# Power.net
KiCad netlist of a schematic drawn in Altium Designer
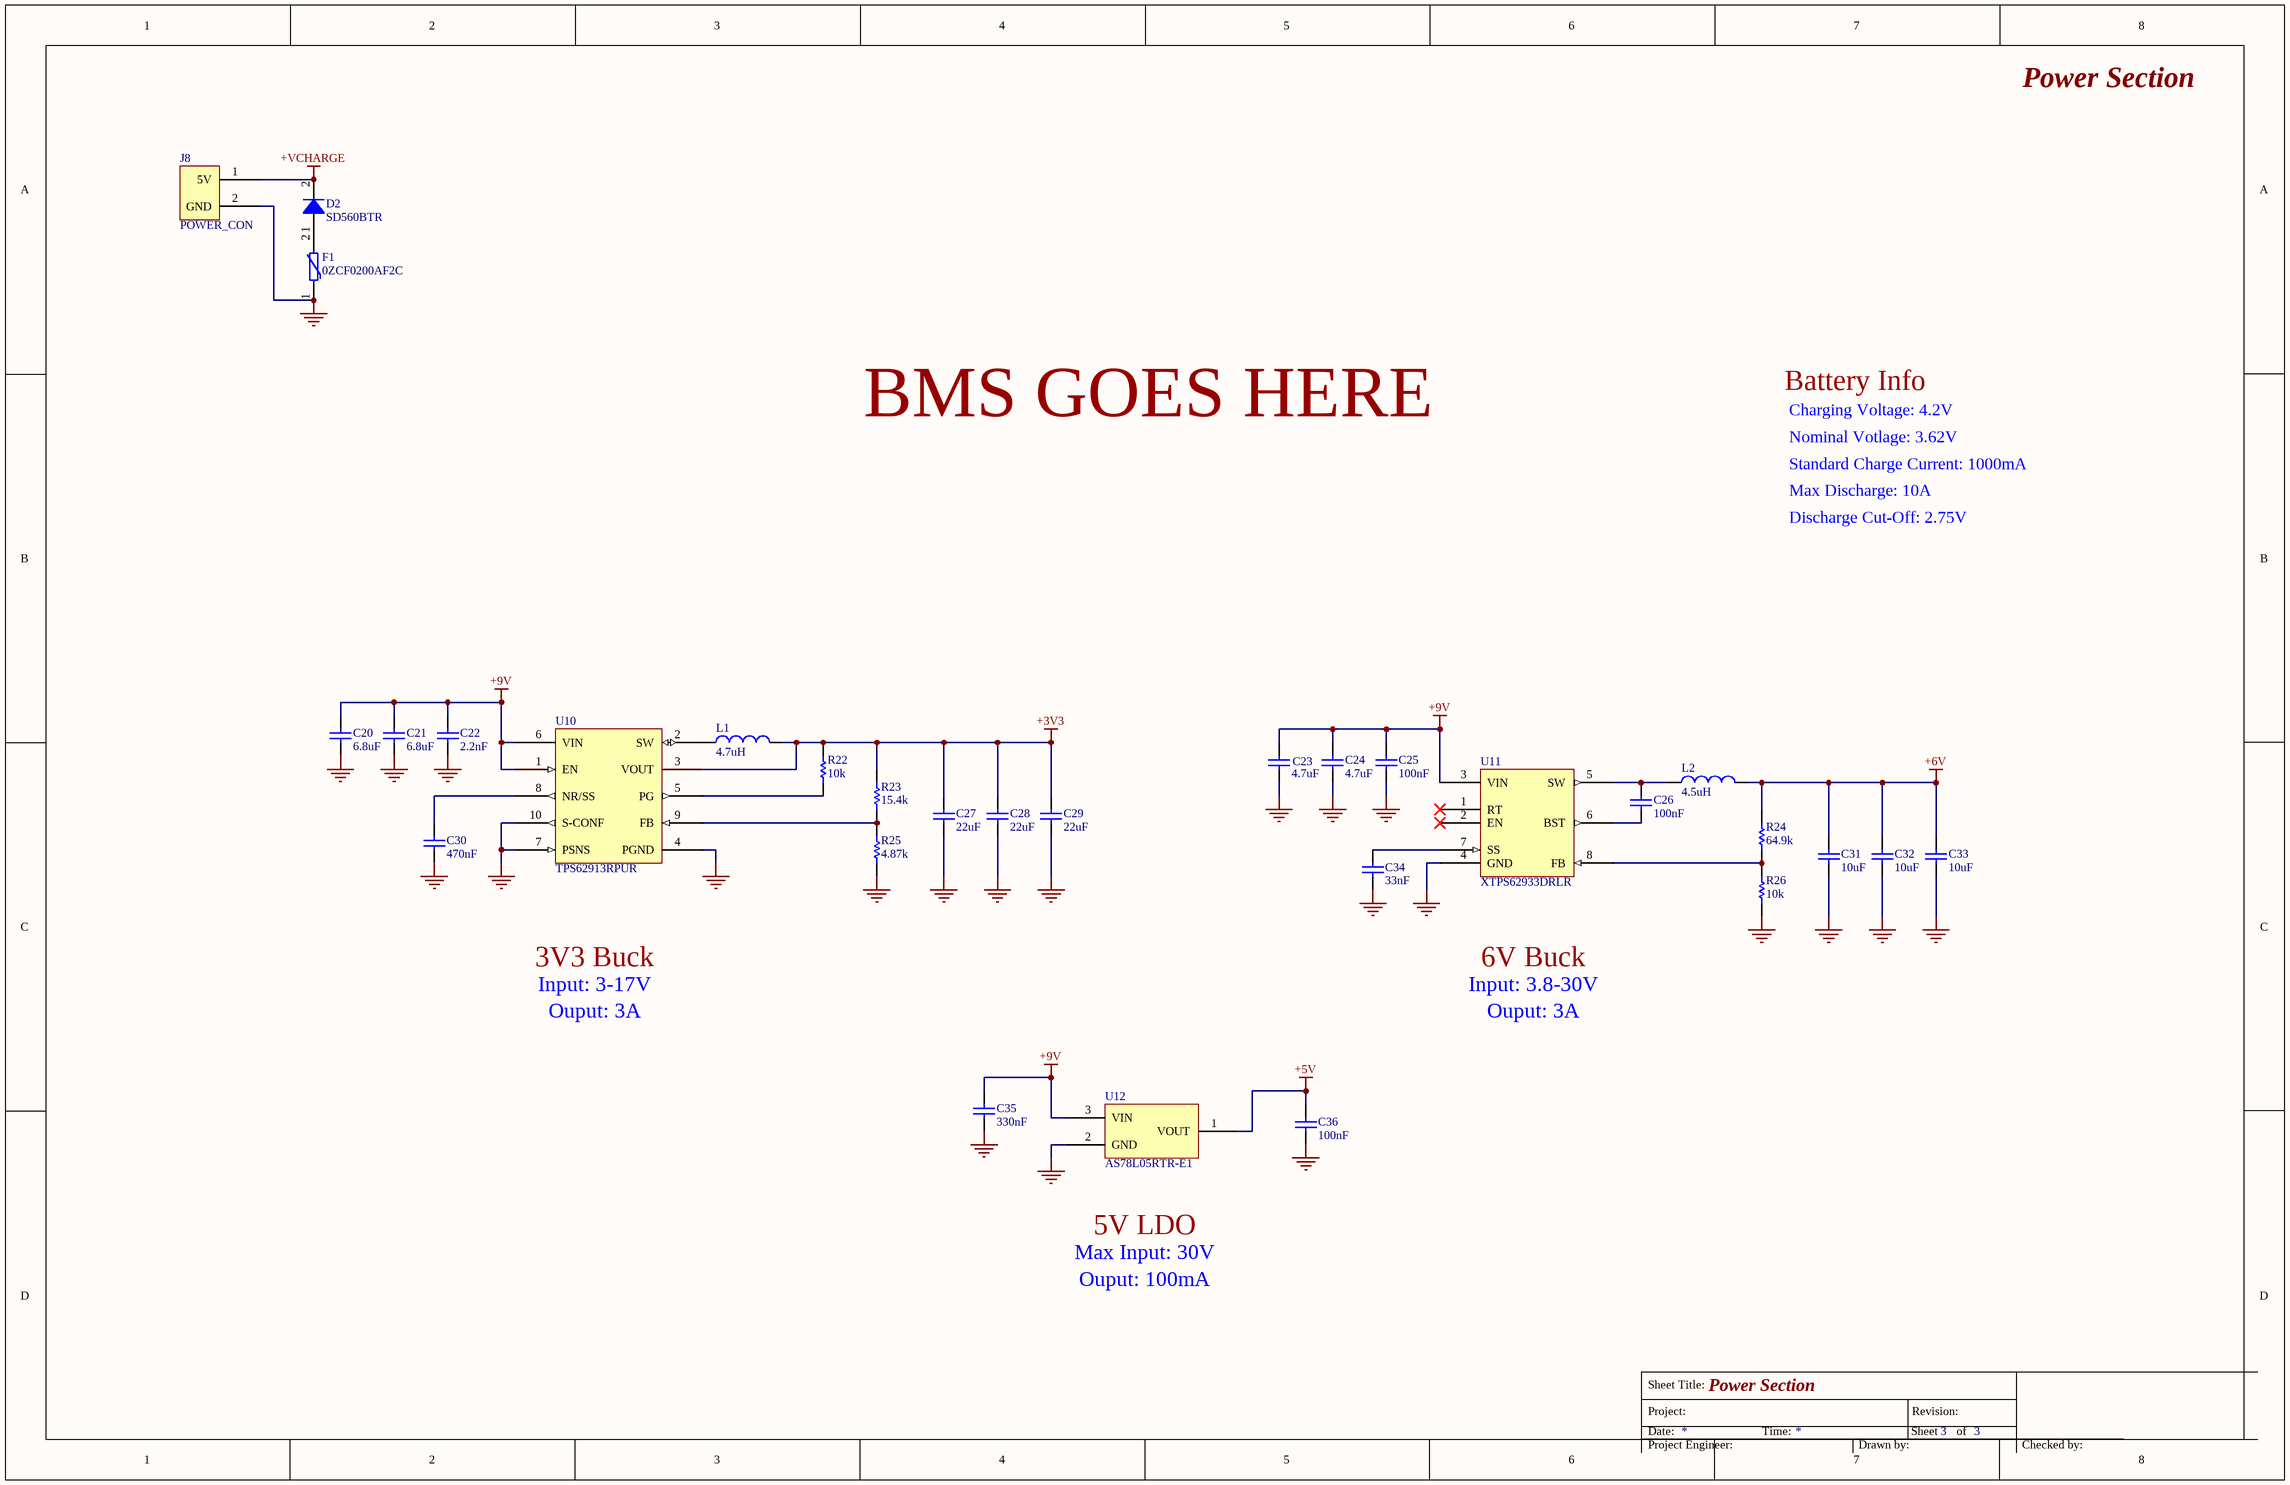
[diagram p0: Power.SchDoc]

(export (version "E")
  (design (tool "Eeschema 10.0.6"))
  (components
    (comp (ref "C20")
      (value "6.8uF")
      (footprint "C0603")
      (description "General Purpose MLCC, 0603, JB, 25V, 6.8 F, 20%, 0.80mm")
      (fields (field (name "PART NUMBER") "C1608JB1E685M080AC") (field (name "MANUFACTURER") "TDK"))
      (libsource (lib "EMRLibrary") (part "EMR_Cap"))
    )
    (comp (ref "C21")
      (value "6.8uF")
      (footprint "C0603")
      (description "General Purpose MLCC, 0603, JB, 25V, 6.8 F, 20%, 0.80mm")
      (fields (field (name "PART NUMBER") "C1608JB1E685M080AC") (field (name "MANUFACTURER") "TDK"))
      (libsource (lib "EMRLibrary") (part "EMR_Cap"))
    )
    (comp (ref "C22")
      (value "2.2nF")
      (footprint "C0402")
      (description "CAP CER 0402 2.2NF 25V C0G 5%")
      (fields (field (name "PART NUMBER") "C0402C222J3GEC7867") (field (name "MANUFACTURER") "KEMET"))
      (libsource (lib "EMRLibrary") (part "EMR_Cap"))
    )
    (comp (ref "C23")
      (value "4.7uF")
      (footprint "C0805")
      (description "4.7µF Ceramic Capacitor 16V % Samsung Electro-Mechanics CL21A475KOFNNNG")
      (fields (field (name "PART NUMBER") "CL21A475KOFNNNG") (field (name "MANUFACTURER") "Samsung"))
      (libsource (lib "EMRLibrary") (part "EMR_Cap"))
    )
    (comp (ref "C24")
      (value "4.7uF")
      (footprint "C0805")
      (description "4.7µF Ceramic Capacitor 16V % Samsung Electro-Mechanics CL21A475KOFNNNG")
      (fields (field (name "PART NUMBER") "CL21A475KOFNNNG") (field (name "MANUFACTURER") "Samsung"))
      (libsource (lib "EMRLibrary") (part "EMR_Cap"))
    )
    (comp (ref "C25")
      (value "100nF")
      (footprint "C0402")
      (fields (field (name "PART NUMBER") "CL05A104KA5NNNC") (field (name "MANUFACTURER") "Samsung"))
      (libsource (lib "EMRLibrary") (part "EMR_Cap"))
    )
    (comp (ref "C26")
      (value "100nF")
      (footprint "C0402")
      (fields (field (name "PART NUMBER") "CL05A104KA5NNNC") (field (name "MANUFACTURER") "Samsung"))
      (libsource (lib "EMRLibrary") (part "EMR_Cap"))
    )
    (comp (ref "C27")
      (value "22uF")
      (footprint "C0603")
      (fields (field (name "PART NUMBER") "CL10A226MPMNUBE") (field (name "MANUFACTURER") "Samsung"))
      (libsource (lib "EMRLibrary") (part "EMR_Cap"))
    )
    (comp (ref "C28")
      (value "22uF")
      (footprint "C0603")
      (fields (field (name "PART NUMBER") "CL10A226MPMNUBE") (field (name "MANUFACTURER") "Samsung"))
      (libsource (lib "EMRLibrary") (part "EMR_Cap"))
    )
    (comp (ref "C29")
      (value "22uF")
      (footprint "C0603")
      (fields (field (name "PART NUMBER") "CL10A226MPMNUBE") (field (name "MANUFACTURER") "Samsung"))
      (libsource (lib "EMRLibrary") (part "EMR_Cap"))
    )
    (comp (ref "C30")
      (value "470nF")
      (footprint "C0402")
      (description "0.47 µF ±10% 10V Ceramic Capacitor X7R 0402 (1005 Metric)")
      (fields (field (name "PART NUMBER") "C0402C474K8RACTU") (field (name "MANUFACTURER") "KEMET"))
      (libsource (lib "EMRLibrary") (part "EMR_Cap"))
    )
    (comp (ref "C31")
      (value "10uF")
      (footprint "C0805")
      (fields (field (name "PART NUMBER") "CL21A106KAYNNNG") (field (name "MANUFACTURER") "Samsung"))
      (libsource (lib "EMRLibrary") (part "EMR_Cap"))
    )
    (comp (ref "C32")
      (value "10uF")
      (footprint "C0805")
      (fields (field (name "PART NUMBER") "CL21A106KAYNNNG") (field (name "MANUFACTURER") "Samsung"))
      (libsource (lib "EMRLibrary") (part "EMR_Cap"))
    )
    (comp (ref "C33")
      (value "10uF")
      (footprint "C0805")
      (fields (field (name "PART NUMBER") "CL21A106KAYNNNG") (field (name "MANUFACTURER") "Samsung"))
      (libsource (lib "EMRLibrary") (part "EMR_Cap"))
    )
    (comp (ref "C34")
      (value "33nF")
      (footprint "C0402")
      (description "CAP CER 0.033UF 50V X7R 0402")
      (fields (field (name "PART NUMBER") "CGA2B3X7R1H333K050BB") (field (name "MANUFACTURER") "TDK"))
      (libsource (lib "EMRLibrary") (part "EMR_Cap"))
    )
    (comp (ref "C35")
      (value "330nF")
      (footprint "C0402")
      (description "CAP CER 0.33UF 35V JB 0402")
      (fields (field (name "PART NUMBER") "C1005JB1V334M050BC") (field (name "MANUFACTURER") "TDK"))
      (libsource (lib "EMRLibrary") (part "EMR_Cap"))
    )
    (comp (ref "C36")
      (value "100nF")
      (footprint "C0402")
      (fields (field (name "PART NUMBER") "CL05A104KA5NNNC") (field (name "MANUFACTURER") "Samsung"))
      (libsource (lib "EMRLibrary") (part "EMR_Cap"))
    )
    (comp (ref "D2")
      (value "SD560BTR")
      (footprint "DIOM4436X26N")
      (description "Diode Gen Purp 600V 5A Smb")
      (fields (field (name "MANUFACTURER") "SMC"))
      (libsource (lib "EMRLibrary") (part "EMR_Diode"))
    )
    (comp (ref "F1")
      (value "0ZCF0200AF2C")
      (footprint "RESC7451X08N")
      (description "PTC RESET FUSE 24V 2A 2920")
      (fields (field (name "MANUFACTURER") "Bel"))
      (libsource (lib "EMRLibrary") (part "EMR_PTC"))
    )
    (comp (ref "J8")
      (value "POWER_CON")
      (description "2 Right angle header pins.")
      (libsource (lib "EMR") (part "POWER_CON"))
    )
    (comp (ref "L1")
      (value "4.7uH")
      (footprint "SPM6530T-4R7M")
      (description "Ind Power Shielded Wirewound 4.7uH 20% 100KHz Metal 5.6A T/R")
      (fields (field (name "PART NUMBER") "SPM6530T-4R7M") (field (name "MANUFACTURER") "TDK"))
      (libsource (lib "EMRLibrary") (part "EMR_Inductor"))
    )
    (comp (ref "L2")
      (value "4.5uH")
      (footprint "SRR1208-4R5ML")
      (description "Inductor;  Filter;  Ind 4.5uH;  Tol 20%;  Cur 6.5A;  SMT;  Case 1208;  DCR 0.014 Ohms")
      (fields (field (name "PART NUMBER") "SRR1208-4R5ML") (field (name "MANUFACTURER") "Bourns"))
      (libsource (lib "EMRLibrary") (part "EMR_Inductor"))
    )
    (comp (ref "R22")
      (value "10k")
      (footprint "RESC1005X04N")
      (description "RES SMD 10K OHM 1% 1/16W 0402")
      (fields (field (name "PART NUMBER") "RC0402FR-0710KL") (field (name "MANUFACTURER") "Yageo"))
      (libsource (lib "EMRLibrary") (part "RC0402"))
    )
    (comp (ref "R23")
      (value "15.4k")
      (footprint "RESC1005X04N")
      (description "RES 15.4K OHM 0.1% 1/10W 0402")
      (fields (field (name "PART NUMBER") "TNPW040215K4BEED") (field (name "MANUFACTURER") "Vishay Dale"))
      (libsource (lib "EMRLibrary") (part "RC0402"))
    )
    (comp (ref "R24")
      (value "64.9k")
      (footprint "RESC1005X04N")
      (description "RES 64.9K OHM 1% 1/16W 0402")
      (fields (field (name "PART NUMBER") "RC0402FR-0764K9L") (field (name "MANUFACTURER") "Yageo"))
      (libsource (lib "EMRLibrary") (part "RC0402"))
    )
    (comp (ref "R25")
      (value "4.87k")
      (footprint "RESC1005X04N")
      (description "Res Thick Film 0402 4.87K Ohm 1% 1/16W 100ppm/C Molded SMD SMD Paper T/R")
      (fields (field (name "PART NUMBER") "RC0402FR-074K87L") (field (name "MANUFACTURER") "Yageo"))
      (libsource (lib "EMRLibrary") (part "RC0402"))
    )
    (comp (ref "R26")
      (value "10k")
      (footprint "RESC1005X04N")
      (description "RES SMD 10K OHM 1% 1/16W 0402")
      (fields (field (name "PART NUMBER") "RC0402FR-0710KL") (field (name "MANUFACTURER") "Yageo"))
      (libsource (lib "EMRLibrary") (part "RC0402"))
    )
    (comp (ref "U10")
      (value "TPS62913RPUR")
      (footprint "TPS62913RPUR")
      (fields (field (name "MANUFACTURER") "Texas Instruments"))
      (libsource (lib "EMRLibrary") (part "TPS62913RPUR"))
    )
    (comp (ref "U11")
      (value "XTPS62933DRLR")
      (footprint "XTPS62933DRLR")
      (description "3.8-V to 30-V, 3-A, 200-kHz to 2.2-MHz, low-IQ synchronous buck converter in SOT-583 package")
      (fields (field (name "MANUFACTURER") "Texas Instruments"))
      (libsource (lib "EMRLibrary") (part "XTPS62933DRLR"))
    )
    (comp (ref "U12")
      (value "AS78L05RTR-E1")
      (footprint "SOT89-150P350X160-3N")
      (description "Standard Regulator Pos 5V 0.1A 3-Pin SOT-89 T/R")
      (fields (field (name "MANUFACTURER") "Diodes"))
      (libsource (lib "EMRLibrary") (part "AS78L05RTR-E1"))
    )
  )
  (nets
    (net (code "1") (name "+3V3") (class "Default")
      (node (ref "C27") (pin "2") (pinfunction "2_2") (pintype "passive"))
      (node (ref "C28") (pin "2") (pinfunction "2_2") (pintype "passive"))
      (node (ref "C29") (pin "2") (pinfunction "2_2") (pintype "passive"))
      (node (ref "L1") (pin "2") (pinfunction "2_2") (pintype "passive"))
      (node (ref "R22") (pin "2") (pinfunction "2_2") (pintype "passive"))
      (node (ref "R23") (pin "2") (pinfunction "2_2") (pintype "passive"))
      (node (ref "U10") (pin "3") (pinfunction "VOUT_3") (pintype "power_in"))
    )
    (net (code "2") (name "+5V") (class "Default")
      (node (ref "C36") (pin "2") (pinfunction "2_2") (pintype "passive"))
      (node (ref "U12") (pin "1") (pinfunction "VOUT_1") (pintype "power_in"))
    )
    (net (code "3") (name "+6V") (class "Default")
      (node (ref "C31") (pin "2") (pinfunction "2_2") (pintype "passive"))
      (node (ref "C32") (pin "2") (pinfunction "2_2") (pintype "passive"))
      (node (ref "C33") (pin "2") (pinfunction "2_2") (pintype "passive"))
      (node (ref "L2") (pin "2") (pinfunction "2_2") (pintype "passive"))
      (node (ref "R24") (pin "2") (pinfunction "2_2") (pintype "passive"))
    )
    (net (code "4") (name "+9V") (class "Default")
      (node (ref "C20") (pin "2") (pinfunction "2_2") (pintype "passive"))
      (node (ref "C21") (pin "2") (pinfunction "2_2") (pintype "passive"))
      (node (ref "C22") (pin "2") (pinfunction "2_2") (pintype "passive"))
      (node (ref "C23") (pin "2") (pinfunction "2_2") (pintype "passive"))
      (node (ref "C24") (pin "2") (pinfunction "2_2") (pintype "passive"))
      (node (ref "C25") (pin "2") (pinfunction "2_2") (pintype "passive"))
      (node (ref "C35") (pin "2") (pinfunction "2_2") (pintype "passive"))
      (node (ref "U10") (pin "1") (pinfunction "EN_1") (pintype "input"))
      (node (ref "U10") (pin "6") (pinfunction "VIN_6") (pintype "power_in"))
      (node (ref "U11") (pin "3") (pinfunction "VIN_3") (pintype "power_in"))
      (node (ref "U12") (pin "3") (pinfunction "VIN_3") (pintype "power_in"))
    )
    (net (code "5") (name "+VCHARGE") (class "Default")
      (node (ref "D2") (pin "2") (pinfunction "K_2") (pintype "passive"))
      (node (ref "J8") (pin "1") (pinfunction "5V_1") (pintype "power_in"))
    )
    (net (code "6") (name "GND") (class "Default")
      (node (ref "C20") (pin "1") (pinfunction "1_1") (pintype "passive"))
      (node (ref "C21") (pin "1") (pinfunction "1_1") (pintype "passive"))
      (node (ref "C22") (pin "1") (pinfunction "1_1") (pintype "passive"))
      (node (ref "C23") (pin "1") (pinfunction "1_1") (pintype "passive"))
      (node (ref "C24") (pin "1") (pinfunction "1_1") (pintype "passive"))
      (node (ref "C25") (pin "1") (pinfunction "1_1") (pintype "passive"))
      (node (ref "C27") (pin "1") (pinfunction "1_1") (pintype "passive"))
      (node (ref "C28") (pin "1") (pinfunction "1_1") (pintype "passive"))
      (node (ref "C29") (pin "1") (pinfunction "1_1") (pintype "passive"))
      (node (ref "C30") (pin "1") (pinfunction "1_1") (pintype "passive"))
      (node (ref "C31") (pin "1") (pinfunction "1_1") (pintype "passive"))
      (node (ref "C32") (pin "1") (pinfunction "1_1") (pintype "passive"))
      (node (ref "C33") (pin "1") (pinfunction "1_1") (pintype "passive"))
      (node (ref "C34") (pin "1") (pinfunction "1_1") (pintype "passive"))
      (node (ref "C35") (pin "1") (pinfunction "1_1") (pintype "passive"))
      (node (ref "C36") (pin "1") (pinfunction "1_1") (pintype "passive"))
      (node (ref "F1") (pin "1") (pinfunction "A_1") (pintype "passive"))
      (node (ref "J8") (pin "2") (pinfunction "GND_2") (pintype "power_in"))
      (node (ref "R25") (pin "1") (pinfunction "1_1") (pintype "passive"))
      (node (ref "R26") (pin "1") (pinfunction "1_1") (pintype "passive"))
      (node (ref "U10") (pin "10") (pinfunction "S-CONF_10") (pintype "output"))
      (node (ref "U10") (pin "4") (pinfunction "PGND_4") (pintype "power_in"))
      (node (ref "U10") (pin "7") (pinfunction "PSNS_7") (pintype "input"))
      (node (ref "U11") (pin "4") (pinfunction "GND_4") (pintype "power_in"))
      (node (ref "U12") (pin "2") (pinfunction "GND_2") (pintype "power_in"))
    )
    (net (code "7") (name "Net-(D2-A)") (class "Default")
      (node (ref "D2") (pin "1") (pinfunction "A_1") (pintype "passive"))
      (node (ref "F1") (pin "2") (pinfunction "K_2") (pintype "passive"))
    )
    (net (code "8") (name "Net-(U10-FB)") (class "Default")
      (node (ref "R23") (pin "1") (pinfunction "1_1") (pintype "passive"))
      (node (ref "R25") (pin "2") (pinfunction "2_2") (pintype "passive"))
      (node (ref "U10") (pin "9") (pinfunction "FB_9") (pintype "input"))
    )
    (net (code "9") (name "Net-(U10-NR{slash}SS)") (class "Default")
      (node (ref "C30") (pin "2") (pinfunction "2_2") (pintype "passive"))
      (node (ref "U10") (pin "8") (pinfunction "NR/SS_8") (pintype "output"))
    )
    (net (code "10") (name "Net-(U10-PG)") (class "Default")
      (node (ref "R22") (pin "1") (pinfunction "1_1") (pintype "passive"))
      (node (ref "U10") (pin "5") (pinfunction "PG_5") (pintype "output"))
    )
    (net (code "11") (name "Net-(U10-SW)") (class "Default")
      (node (ref "L1") (pin "1") (pinfunction "1_1") (pintype "passive"))
      (node (ref "U10") (pin "2") (pinfunction "SW_2") (pintype "bidirectional"))
    )
    (net (code "12") (name "Net-(U11-BST)") (class "Default")
      (node (ref "C26") (pin "1") (pinfunction "1_1") (pintype "passive"))
      (node (ref "U11") (pin "6") (pinfunction "BST_6") (pintype "output"))
    )
    (net (code "13") (name "Net-(U11-FB)") (class "Default")
      (node (ref "R24") (pin "1") (pinfunction "1_1") (pintype "passive"))
      (node (ref "R26") (pin "2") (pinfunction "2_2") (pintype "passive"))
      (node (ref "U11") (pin "8") (pinfunction "FB_8") (pintype "input"))
    )
    (net (code "14") (name "Net-(U11-SS)") (class "Default")
      (node (ref "C34") (pin "2") (pinfunction "2_2") (pintype "passive"))
      (node (ref "U11") (pin "7") (pinfunction "SS_7") (pintype "input"))
    )
    (net (code "15") (name "Net-(U11-SW)") (class "Default")
      (node (ref "C26") (pin "2") (pinfunction "2_2") (pintype "passive"))
      (node (ref "L2") (pin "1") (pinfunction "1_1") (pintype "passive"))
      (node (ref "U11") (pin "5") (pinfunction "SW_5") (pintype "output"))
    )
    (net (code "16") (name "unconnected-(U11-EN-Pad2)") (class "Default")
      (node (ref "U11") (pin "2") (pinfunction "EN_2") (pintype "passive+no_connect"))
    )
    (net (code "17") (name "unconnected-(U11-RT-Pad1)") (class "Default")
      (node (ref "U11") (pin "1") (pinfunction "RT_1") (pintype "passive+no_connect"))
    )
  )
)
